# AVRcam.net
KiCad netlist of a schematic drawn in EAGLE
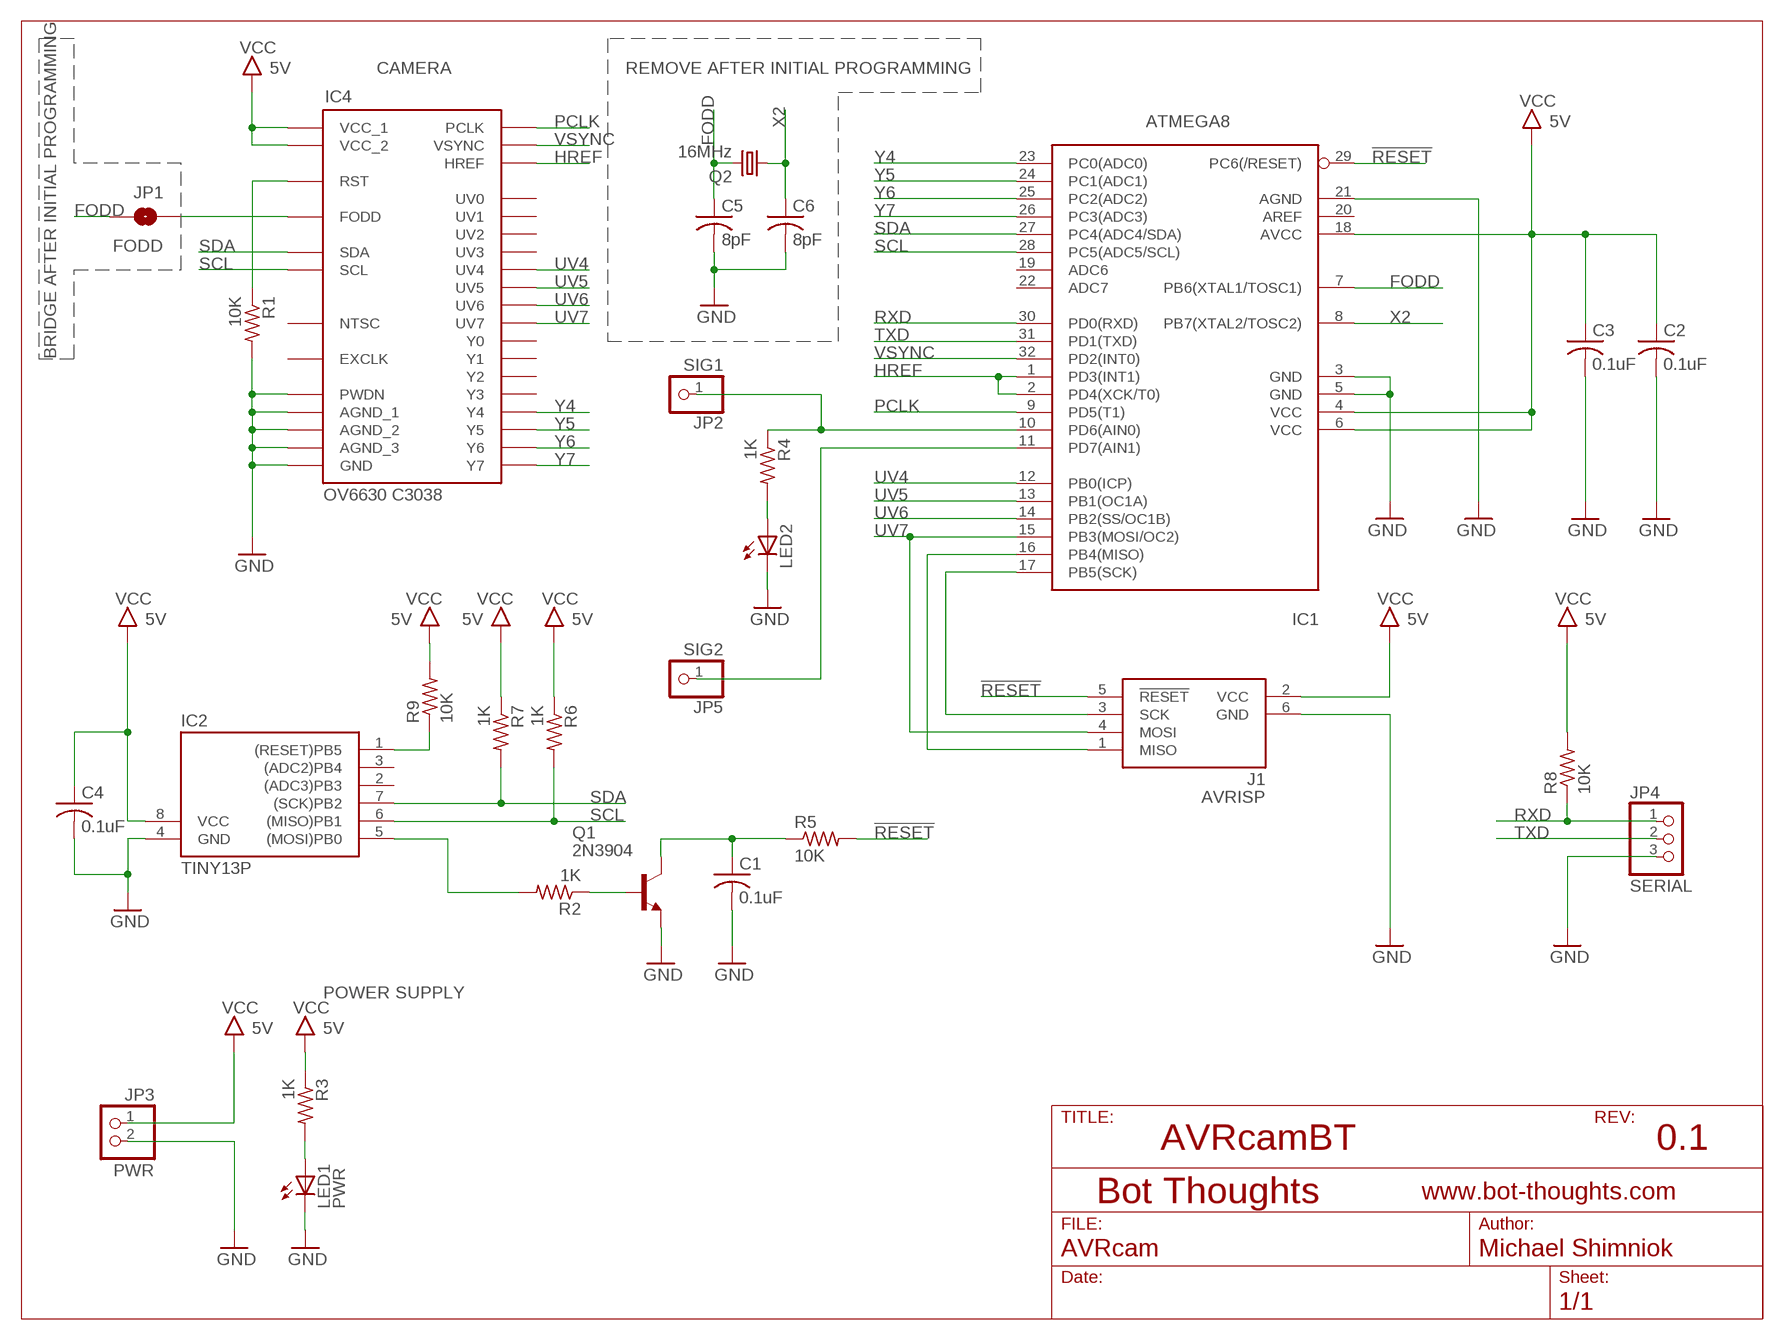
[diagram p0: schematic, sheet 1]

(export (version "E")
  (design (tool "Eeschema 10.0.6"))
  (components
    (comp (ref "C1")
      (value "0.1uF")
      (footprint "eagle-import:C0603")
      (fields (field (name "PARTNO") "CC0603ZRY5V9BB104"))
      (libsource (lib "eagle-import") (part "C-USC0603"))
    )
    (comp (ref "C2")
      (value "0.1uF")
      (footprint "eagle-import:C0603")
      (fields (field (name "PARTNO") "CC0603ZRY5V9BB104"))
      (libsource (lib "eagle-import") (part "C-USC0603"))
    )
    (comp (ref "C3")
      (value "0.1uF")
      (footprint "eagle-import:C0603")
      (fields (field (name "PARTNO") "CC0603ZRY5V9BB104"))
      (libsource (lib "eagle-import") (part "C-USC0603"))
    )
    (comp (ref "C4")
      (value "0.1uF")
      (footprint "eagle-import:C0603")
      (fields (field (name "PARTNO") "CC0603ZRY5V9BB104"))
      (libsource (lib "eagle-import") (part "C-USC0603"))
    )
    (comp (ref "C5")
      (value "8pF")
      (footprint "eagle-import:C0603")
      (fields (field (name "PARTNO") "C1608C0G1H080D"))
      (libsource (lib "eagle-import") (part "C-USC0603"))
    )
    (comp (ref "C6")
      (value "8pF")
      (footprint "eagle-import:C0603")
      (fields (field (name "PARTNO") "C1608C0G1H080D"))
      (libsource (lib "eagle-import") (part "C-USC0603"))
    )
    (comp (ref "IC1")
      (value "ATMEGA8")
      (footprint "eagle-import:TQFP32-08")
      (fields (field (name "PARTNO") "ATMEGA8A-AU"))
      (libsource (lib "eagle-import") (part "MEGA8-AI"))
    )
    (comp (ref "IC2")
      (value "TINY13P")
      (footprint "eagle-import:DIL08")
      (fields (field (name "PARTNO") "ATTINY13V-10PU"))
      (libsource (lib "eagle-import") (part "TINY12P"))
    )
    (comp (ref "IC4")
      (value "OV6630 C3038")
      (footprint "eagle-import:C3038_C3X88_C3088")
      (libsource (lib "eagle-import") (part "OV6620C3038"))
    )
    (comp (ref "J1")
      (value "AVRISP")
      (footprint "eagle-import:CON6P2R")
      (libsource (lib "eagle-import") (part "AVRISP6"))
    )
    (comp (ref "JP1")
      (value "FODD")
      (footprint "eagle-import:SJ_2S-NO")
      (libsource (lib "eagle-import") (part "SOLDERJUMPERNO"))
    )
    (comp (ref "JP2")
      (value "SIG1")
      (footprint "eagle-import:1X01")
      (libsource (lib "eagle-import") (part "PINHD-1X01_2.54"))
    )
    (comp (ref "JP3")
      (value "PWR")
      (footprint "eagle-import:1X02-S")
      (libsource (lib "eagle-import") (part "PINHD-1X02_2.54-S"))
    )
    (comp (ref "JP4")
      (value "SERIAL")
      (footprint "eagle-import:1X03-S")
      (libsource (lib "eagle-import") (part "PINHD-1X03_2.54-S"))
    )
    (comp (ref "JP5")
      (value "SIG2")
      (footprint "eagle-import:1X01")
      (libsource (lib "eagle-import") (part "PINHD-1X01_2.54"))
    )
    (comp (ref "LED1")
      (value "PWR")
      (footprint "eagle-import:CHIP-LED0805")
      (fields (field (name "PARTNO") "APT2012EC"))
      (libsource (lib "eagle-import") (part "LEDCHIP-LED0805"))
    )
    (comp (ref "LED2")
      (value "LEDCHIP-LED0805")
      (footprint "eagle-import:CHIP-LED0805")
      (fields (field (name "PARTNO") "APT2012SGC"))
      (libsource (lib "eagle-import") (part "LEDCHIP-LED0805"))
    )
    (comp (ref "Q1")
      (value "2N3904")
      (footprint "eagle-import:SOT-23")
      (fields (field (name "PARTNO") "MMBT3904-7-F"))
      (libsource (lib "eagle-import") (part "2N3904SMD"))
    )
    (comp (ref "Q2")
      (value "16MHz")
      (footprint "eagle-import:NDK_2PAD_5X3")
      (fields (field (name "PARTNO") "NX5032GA-16.000000MHZ-LN-CD-1"))
      (libsource (lib "eagle-import") (part "CRYSTALNDK5X3"))
    )
    (comp (ref "R1")
      (value "10K")
      (footprint "eagle-import:R0603")
      (fields (field (name "PARTNO") "ERJ-3GEYJ103V"))
      (libsource (lib "eagle-import") (part "R-US_R0603"))
    )
    (comp (ref "R2")
      (value "1K")
      (footprint "eagle-import:R0603")
      (fields (field (name "PARTNO") "ERJ-3GEYJ102V"))
      (libsource (lib "eagle-import") (part "R-US_R0603"))
    )
    (comp (ref "R3")
      (value "1K")
      (footprint "eagle-import:R0603")
      (fields (field (name "PARTNO") "ERJ-3GEYJ102V"))
      (libsource (lib "eagle-import") (part "R-US_R0603"))
    )
    (comp (ref "R4")
      (value "1K")
      (footprint "eagle-import:R0603")
      (fields (field (name "PARTNO") "ERJ-3GEYJ102V"))
      (libsource (lib "eagle-import") (part "R-US_R0603"))
    )
    (comp (ref "R5")
      (value "10K")
      (footprint "eagle-import:R0603")
      (fields (field (name "PARTNO") "ERJ-3GEYJ103V"))
      (libsource (lib "eagle-import") (part "R-US_R0603"))
    )
    (comp (ref "R6")
      (value "1K")
      (footprint "eagle-import:R0603")
      (fields (field (name "PARTNO") "ERJ-3GEYJ102V"))
      (libsource (lib "eagle-import") (part "R-US_R0603"))
    )
    (comp (ref "R7")
      (value "1K")
      (footprint "eagle-import:R0603")
      (fields (field (name "PARTNO") "ERJ-3GEYJ102V"))
      (libsource (lib "eagle-import") (part "R-US_R0603"))
    )
    (comp (ref "R8")
      (value "10K")
      (footprint "eagle-import:R0603")
      (fields (field (name "PARTNO") "ERJ-3GEYJ103V"))
      (libsource (lib "eagle-import") (part "R-US_R0603"))
    )
    (comp (ref "R9")
      (value "10K")
      (footprint "eagle-import:R0603")
      (fields (field (name "PARTNO") "ERJ-3GEYJ103V"))
      (libsource (lib "eagle-import") (part "R-US_R0603"))
    )
  )
  (nets
    (net (code "1") (name "/FODD") (class "Default")
      (node (ref "C5") (pin "1") (pinfunction "1_1") (pintype "passive"))
      (node (ref "IC1") (pin "7") (pinfunction "PB6(XTAL1/TOSC1)_7") (pintype "bidirectional"))
      (node (ref "JP1") (pin "2") (pinfunction "2_2") (pintype "passive"))
      (node (ref "Q2") (pin "P$2") (pinfunction "2_P$2") (pintype "passive"))
    )
    (net (code "2") (name "/HREF") (class "Default")
      (node (ref "IC1") (pin "1") (pinfunction "PD3(INT1)_1") (pintype "bidirectional"))
      (node (ref "IC1") (pin "2") (pinfunction "PD4(XCK/T0)_2") (pintype "bidirectional"))
      (node (ref "IC4") (pin "P$14") (pinfunction "HREF_P$14") (pintype "bidirectional"))
    )
    (net (code "3") (name "/PCLK") (class "Default")
      (node (ref "IC1") (pin "9") (pinfunction "PD5(T1)_9") (pintype "bidirectional"))
      (node (ref "IC4") (pin "P$18") (pinfunction "PCLK_P$18") (pintype "bidirectional"))
    )
    (net (code "4") (name "/RXD") (class "Default")
      (node (ref "IC1") (pin "30") (pinfunction "PD0(RXD)_30") (pintype "bidirectional"))
      (node (ref "JP4") (pin "1") (pinfunction "1_1") (pintype "passive"))
      (node (ref "R8") (pin "1") (pinfunction "1_1") (pintype "passive"))
    )
    (net (code "5") (name "/SCL") (class "Default")
      (node (ref "IC1") (pin "28") (pinfunction "PC5(ADC5/SCL)_28") (pintype "bidirectional"))
      (node (ref "IC2") (pin "6") (pinfunction "(MISO)PB1_6") (pintype "bidirectional"))
      (node (ref "IC4") (pin "P$13") (pinfunction "SCL_P$13") (pintype "bidirectional"))
      (node (ref "R6") (pin "2") (pinfunction "2_2") (pintype "passive"))
    )
    (net (code "6") (name "/SDA") (class "Default")
      (node (ref "IC1") (pin "27") (pinfunction "PC4(ADC4/SDA)_27") (pintype "bidirectional"))
      (node (ref "IC2") (pin "7") (pinfunction "(SCK)PB2_7") (pintype "bidirectional"))
      (node (ref "IC4") (pin "P$11") (pinfunction "SDA_P$11") (pintype "bidirectional"))
      (node (ref "R7") (pin "2") (pinfunction "2_2") (pintype "passive"))
    )
    (net (code "7") (name "/TXD") (class "Default")
      (node (ref "IC1") (pin "31") (pinfunction "PD1(TXD)_31") (pintype "bidirectional"))
      (node (ref "JP4") (pin "2") (pinfunction "2_2") (pintype "passive"))
    )
    (net (code "8") (name "/UV4") (class "Default")
      (node (ref "IC1") (pin "12") (pinfunction "PB0(ICP)_12") (pintype "bidirectional"))
      (node (ref "IC4") (pin "P$27") (pinfunction "UV4_P$27") (pintype "bidirectional"))
    )
    (net (code "9") (name "/UV5") (class "Default")
      (node (ref "IC1") (pin "13") (pinfunction "PB1(OC1A)_13") (pintype "bidirectional"))
      (node (ref "IC4") (pin "P$28") (pinfunction "UV5_P$28") (pintype "bidirectional"))
    )
    (net (code "10") (name "/UV6") (class "Default")
      (node (ref "IC1") (pin "14") (pinfunction "PB2(SS/OC1B)_14") (pintype "bidirectional"))
      (node (ref "IC4") (pin "P$29") (pinfunction "UV6_P$29") (pintype "bidirectional"))
    )
    (net (code "11") (name "/UV7") (class "Default")
      (node (ref "IC1") (pin "15") (pinfunction "PB3(MOSI/OC2)_15") (pintype "bidirectional"))
      (node (ref "IC4") (pin "P$30") (pinfunction "UV7_P$30") (pintype "bidirectional"))
      (node (ref "J1") (pin "4") (pinfunction "MOSI_4") (pintype "output"))
    )
    (net (code "12") (name "/VSYNC") (class "Default")
      (node (ref "IC1") (pin "32") (pinfunction "PD2(INT0)_32") (pintype "bidirectional"))
      (node (ref "IC4") (pin "P$16") (pinfunction "VSYNC_P$16") (pintype "bidirectional"))
    )
    (net (code "13") (name "/X2") (class "Default")
      (node (ref "C6") (pin "1") (pinfunction "1_1") (pintype "passive"))
      (node (ref "IC1") (pin "8") (pinfunction "PB7(XTAL2/TOSC2)_8") (pintype "bidirectional"))
      (node (ref "Q2") (pin "P$1") (pinfunction "1_P$1") (pintype "passive"))
    )
    (net (code "14") (name "/Y4") (class "Default")
      (node (ref "IC1") (pin "23") (pinfunction "PC0(ADC0)_23") (pintype "bidirectional"))
      (node (ref "IC4") (pin "P$5") (pinfunction "Y4_P$5") (pintype "bidirectional"))
    )
    (net (code "15") (name "/Y5") (class "Default")
      (node (ref "IC1") (pin "24") (pinfunction "PC1(ADC1)_24") (pintype "bidirectional"))
      (node (ref "IC4") (pin "P$6") (pinfunction "Y5_P$6") (pintype "bidirectional"))
    )
    (net (code "16") (name "/Y6") (class "Default")
      (node (ref "IC1") (pin "25") (pinfunction "PC2(ADC2)_25") (pintype "bidirectional"))
      (node (ref "IC4") (pin "P$7") (pinfunction "Y6_P$7") (pintype "bidirectional"))
    )
    (net (code "17") (name "/Y7") (class "Default")
      (node (ref "IC1") (pin "26") (pinfunction "PC3(ADC3)_26") (pintype "bidirectional"))
      (node (ref "IC4") (pin "P$8") (pinfunction "Y7_P$8") (pintype "bidirectional"))
    )
    (net (code "18") (name "/~{RESET}") (class "Default")
      (node (ref "IC1") (pin "29") (pinfunction "PC6(/RESET)_29") (pintype "bidirectional"))
      (node (ref "J1") (pin "5") (pinfunction "~{RESET}_5") (pintype "output"))
      (node (ref "R5") (pin "2") (pinfunction "2_2") (pintype "passive"))
    )
    (net (code "19") (name "5V") (class "Default")
      (node (ref "C2") (pin "1") (pinfunction "1_1") (pintype "passive"))
      (node (ref "C3") (pin "1") (pinfunction "1_1") (pintype "passive"))
      (node (ref "C4") (pin "1") (pinfunction "1_1") (pintype "passive"))
      (node (ref "IC1") (pin "18") (pinfunction "AVCC_18") (pintype "bidirectional"))
      (node (ref "IC1") (pin "4") (pinfunction "VCC_4") (pintype "bidirectional"))
      (node (ref "IC1") (pin "6") (pinfunction "VCC_6") (pintype "bidirectional"))
      (node (ref "IC2") (pin "8") (pinfunction "VCC_8") (pintype "power_in"))
      (node (ref "IC4") (pin "P$20") (pinfunction "VCC_1_P$20") (pintype "bidirectional"))
      (node (ref "IC4") (pin "P$22") (pinfunction "VCC_2_P$22") (pintype "bidirectional"))
      (node (ref "J1") (pin "2") (pinfunction "VCC_2") (pintype "power_in"))
      (node (ref "JP3") (pin "1") (pinfunction "1_1") (pintype "passive"))
      (node (ref "R3") (pin "1") (pinfunction "1_1") (pintype "passive"))
      (node (ref "R6") (pin "1") (pinfunction "1_1") (pintype "passive"))
      (node (ref "R7") (pin "1") (pinfunction "1_1") (pintype "passive"))
      (node (ref "R8") (pin "2") (pinfunction "2_2") (pintype "passive"))
      (node (ref "R9") (pin "2") (pinfunction "2_2") (pintype "passive"))
    )
    (net (code "20") (name "GND") (class "Default")
      (node (ref "C1") (pin "2") (pinfunction "2_2") (pintype "passive"))
      (node (ref "C2") (pin "2") (pinfunction "2_2") (pintype "passive"))
      (node (ref "C3") (pin "2") (pinfunction "2_2") (pintype "passive"))
      (node (ref "C4") (pin "2") (pinfunction "2_2") (pintype "passive"))
      (node (ref "C5") (pin "2") (pinfunction "2_2") (pintype "passive"))
      (node (ref "C6") (pin "2") (pinfunction "2_2") (pintype "passive"))
      (node (ref "IC1") (pin "21") (pinfunction "AGND_21") (pintype "bidirectional"))
      (node (ref "IC1") (pin "3") (pinfunction "GND_3") (pintype "bidirectional"))
      (node (ref "IC1") (pin "5") (pinfunction "GND_5") (pintype "bidirectional"))
      (node (ref "IC2") (pin "4") (pinfunction "GND_4") (pintype "power_in"))
      (node (ref "IC4") (pin "P$15") (pinfunction "AGND_1_P$15") (pintype "bidirectional"))
      (node (ref "IC4") (pin "P$17") (pinfunction "AGND_2_P$17") (pintype "bidirectional"))
      (node (ref "IC4") (pin "P$21") (pinfunction "AGND_3_P$21") (pintype "bidirectional"))
      (node (ref "IC4") (pin "P$31") (pinfunction "GND_P$31") (pintype "bidirectional"))
      (node (ref "IC4") (pin "P$9") (pinfunction "PWDN_P$9") (pintype "bidirectional"))
      (node (ref "J1") (pin "6") (pinfunction "GND_6") (pintype "power_in"))
      (node (ref "JP3") (pin "2") (pinfunction "2_2") (pintype "passive"))
      (node (ref "JP4") (pin "3") (pinfunction "3_3") (pintype "passive"))
      (node (ref "LED1") (pin "C") (pinfunction "C_C") (pintype "passive"))
      (node (ref "LED2") (pin "C") (pinfunction "C_C") (pintype "passive"))
      (node (ref "Q1") (pin "2") (pinfunction "E_2") (pintype "passive"))
      (node (ref "R1") (pin "2") (pinfunction "2_2") (pintype "passive"))
    )
    (net (code "21") (name "Net-(IC1-PB4(MISO))") (class "Default")
      (node (ref "IC1") (pin "16") (pinfunction "PB4(MISO)_16") (pintype "bidirectional"))
      (node (ref "J1") (pin "1") (pinfunction "MISO_1") (pintype "input"))
    )
    (net (code "22") (name "Net-(IC1-PB5(SCK))") (class "Default")
      (node (ref "IC1") (pin "17") (pinfunction "PB5(SCK)_17") (pintype "bidirectional"))
      (node (ref "J1") (pin "3") (pinfunction "SCK_3") (pintype "output"))
    )
    (net (code "23") (name "Net-(IC1-PD6(AIN0))") (class "Default")
      (node (ref "IC1") (pin "10") (pinfunction "PD6(AIN0)_10") (pintype "bidirectional"))
      (node (ref "JP2") (pin "1") (pinfunction "1_1") (pintype "passive"))
      (node (ref "R4") (pin "1") (pinfunction "1_1") (pintype "passive"))
    )
    (net (code "24") (name "Net-(IC1-PD7(AIN1))") (class "Default")
      (node (ref "IC1") (pin "11") (pinfunction "PD7(AIN1)_11") (pintype "bidirectional"))
      (node (ref "JP5") (pin "1") (pinfunction "1_1") (pintype "passive"))
    )
    (net (code "25") (name "Net-(IC2-(MOSI)PB0)") (class "Default")
      (node (ref "IC2") (pin "5") (pinfunction "(MOSI)PB0_5") (pintype "bidirectional"))
      (node (ref "R2") (pin "2") (pinfunction "2_2") (pintype "passive"))
    )
    (net (code "26") (name "Net-(IC2-(RESET)PB5)") (class "Default")
      (node (ref "IC2") (pin "1") (pinfunction "(RESET)PB5_1") (pintype "bidirectional"))
      (node (ref "R9") (pin "1") (pinfunction "1_1") (pintype "passive"))
    )
    (net (code "27") (name "Net-(IC4-FODD)") (class "Default")
      (node (ref "IC4") (pin "P$12") (pinfunction "FODD_P$12") (pintype "bidirectional"))
      (node (ref "JP1") (pin "1") (pinfunction "1_1") (pintype "passive"))
    )
    (net (code "28") (name "Net-(IC4-RST)") (class "Default")
      (node (ref "IC4") (pin "P$10") (pinfunction "RST_P$10") (pintype "bidirectional"))
      (node (ref "R1") (pin "1") (pinfunction "1_1") (pintype "passive"))
    )
    (net (code "29") (name "Net-(LED1-PadA)") (class "Default")
      (node (ref "LED1") (pin "A") (pinfunction "A_A") (pintype "passive"))
      (node (ref "R3") (pin "2") (pinfunction "2_2") (pintype "passive"))
    )
    (net (code "30") (name "Net-(LED2-PadA)") (class "Default")
      (node (ref "LED2") (pin "A") (pinfunction "A_A") (pintype "passive"))
      (node (ref "R4") (pin "2") (pinfunction "2_2") (pintype "passive"))
    )
    (net (code "31") (name "Net-(Q1-B)") (class "Default")
      (node (ref "Q1") (pin "3") (pinfunction "B_3") (pintype "passive"))
      (node (ref "R2") (pin "1") (pinfunction "1_1") (pintype "passive"))
    )
    (net (code "32") (name "Net-(Q1-C)") (class "Default")
      (node (ref "C1") (pin "1") (pinfunction "1_1") (pintype "passive"))
      (node (ref "Q1") (pin "1") (pinfunction "C_1") (pintype "passive"))
      (node (ref "R5") (pin "1") (pinfunction "1_1") (pintype "passive"))
    )
    (net (code "33") (name "unconnected-(IC1-ADC6-Pad19)") (class "Default")
      (node (ref "IC1") (pin "19") (pinfunction "ADC6_19") (pintype "bidirectional"))
    )
    (net (code "34") (name "unconnected-(IC1-ADC7-Pad22)") (class "Default")
      (node (ref "IC1") (pin "22") (pinfunction "ADC7_22") (pintype "bidirectional"))
    )
    (net (code "35") (name "unconnected-(IC1-AREF-Pad20)") (class "Default")
      (node (ref "IC1") (pin "20") (pinfunction "AREF_20") (pintype "bidirectional"))
    )
    (net (code "36") (name "unconnected-(IC2-(ADC2)PB4-Pad3)") (class "Default")
      (node (ref "IC2") (pin "3") (pinfunction "(ADC2)PB4_3") (pintype "bidirectional"))
    )
    (net (code "37") (name "unconnected-(IC2-(ADC3)PB3-Pad2)") (class "Default")
      (node (ref "IC2") (pin "2") (pinfunction "(ADC3)PB3_2") (pintype "bidirectional"))
    )
    (net (code "38") (name "unconnected-(IC4-EXCLK-PadP$19)") (class "Default")
      (node (ref "IC4") (pin "P$19") (pinfunction "EXCLK_P$19") (pintype "bidirectional"))
    )
    (net (code "39") (name "unconnected-(IC4-NTSC-PadP$32)") (class "Default")
      (node (ref "IC4") (pin "P$32") (pinfunction "NTSC_P$32") (pintype "bidirectional"))
    )
    (net (code "40") (name "unconnected-(IC4-UV0-PadP$23)") (class "Default")
      (node (ref "IC4") (pin "P$23") (pinfunction "UV0_P$23") (pintype "bidirectional"))
    )
    (net (code "41") (name "unconnected-(IC4-UV1-PadP$24)") (class "Default")
      (node (ref "IC4") (pin "P$24") (pinfunction "UV1_P$24") (pintype "bidirectional"))
    )
    (net (code "42") (name "unconnected-(IC4-UV2-PadP$25)") (class "Default")
      (node (ref "IC4") (pin "P$25") (pinfunction "UV2_P$25") (pintype "bidirectional"))
    )
    (net (code "43") (name "unconnected-(IC4-UV3-PadP$26)") (class "Default")
      (node (ref "IC4") (pin "P$26") (pinfunction "UV3_P$26") (pintype "bidirectional"))
    )
    (net (code "44") (name "unconnected-(IC4-Y0-PadP$1)") (class "Default")
      (node (ref "IC4") (pin "P$1") (pinfunction "Y0_P$1") (pintype "bidirectional"))
    )
    (net (code "45") (name "unconnected-(IC4-Y1-PadP$2)") (class "Default")
      (node (ref "IC4") (pin "P$2") (pinfunction "Y1_P$2") (pintype "bidirectional"))
    )
    (net (code "46") (name "unconnected-(IC4-Y2-PadP$3)") (class "Default")
      (node (ref "IC4") (pin "P$3") (pinfunction "Y2_P$3") (pintype "bidirectional"))
    )
    (net (code "47") (name "unconnected-(IC4-Y3-PadP$4)") (class "Default")
      (node (ref "IC4") (pin "P$4") (pinfunction "Y3_P$4") (pintype "bidirectional"))
    )
  )
)
